# R1075B.net
KiCad netlist of a schematic drawn in EAGLE
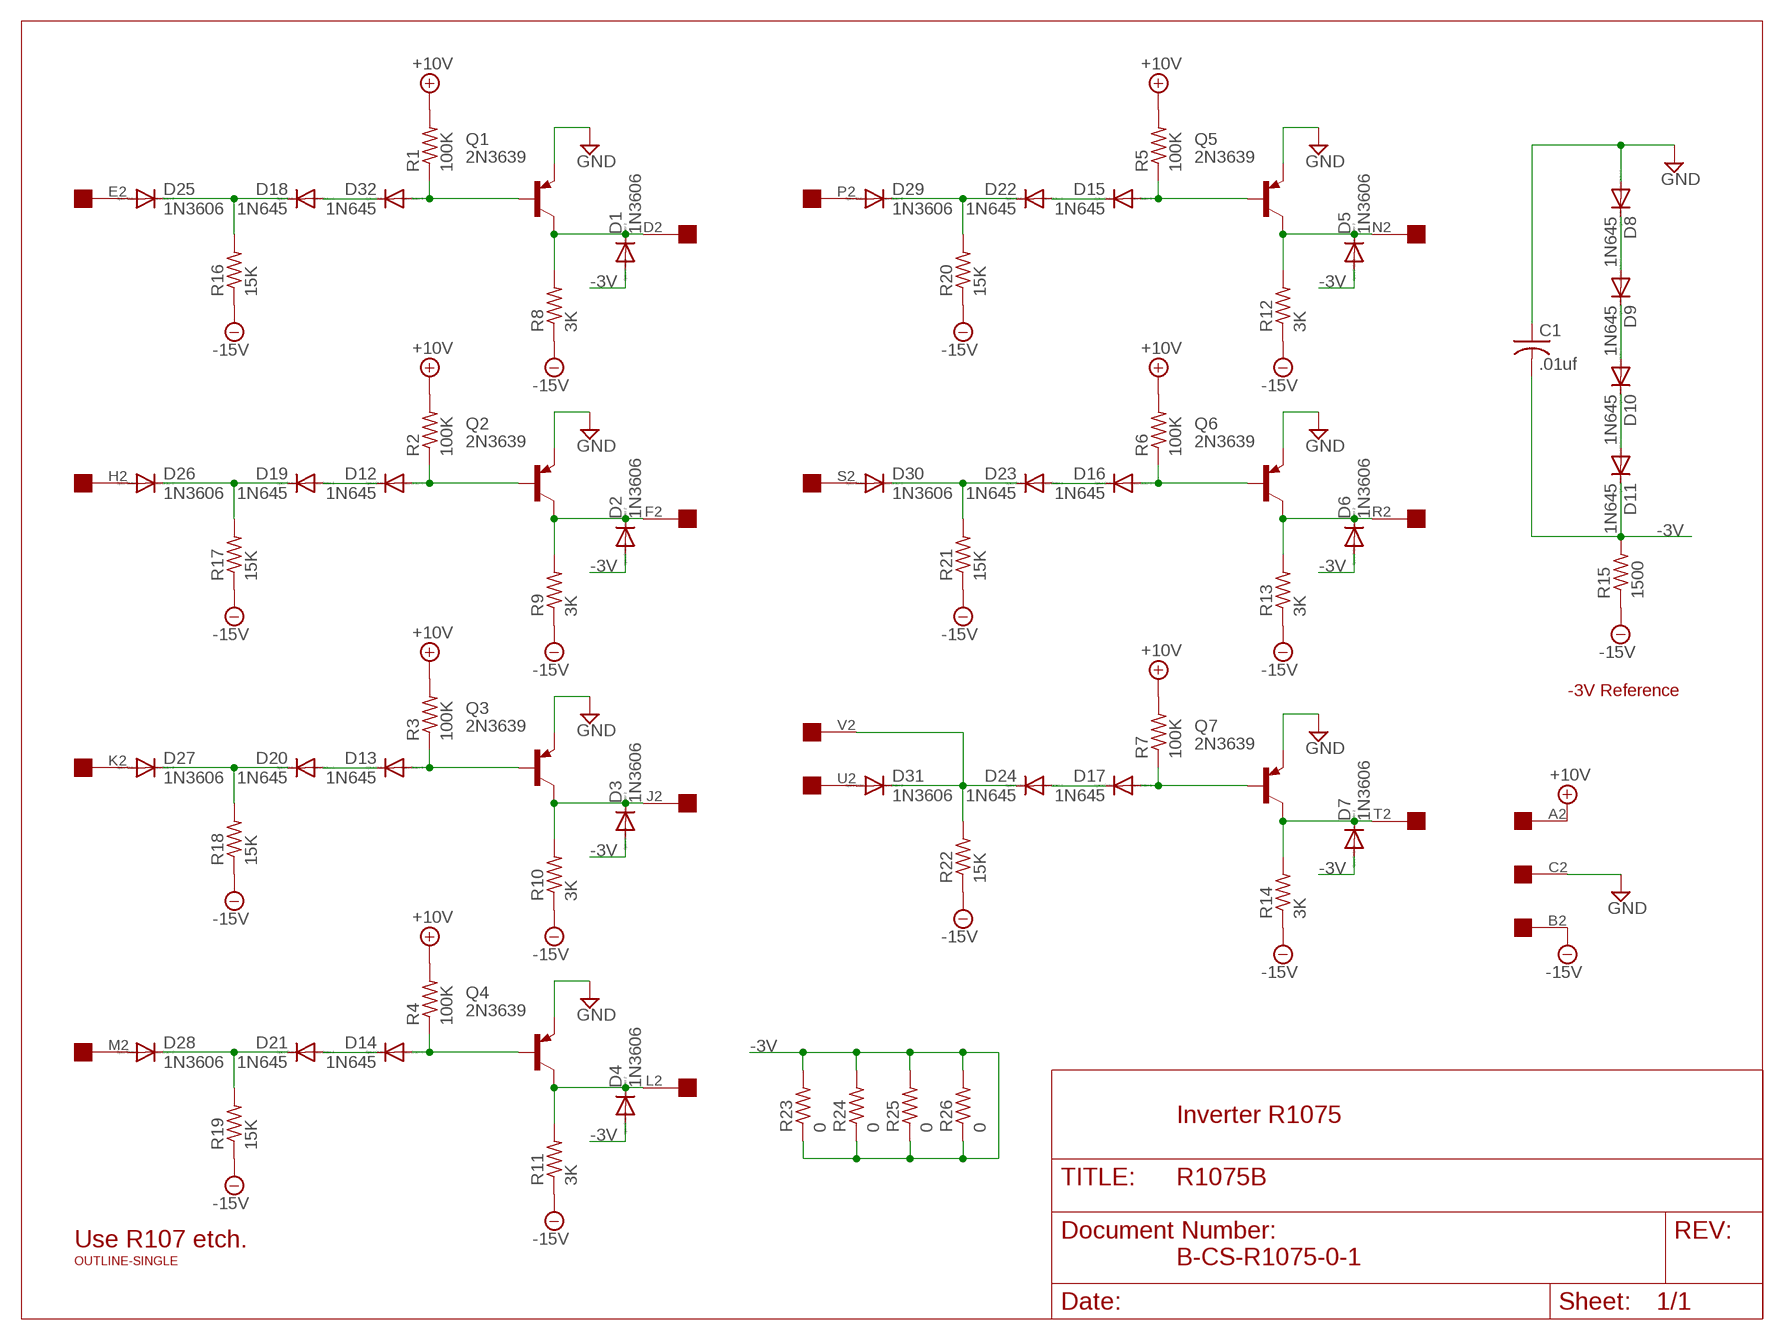
[diagram p0: schematic, sheet 1]

(export (version "E")
  (design (tool "Eeschema 10.0.6"))
  (components
    (comp (ref "C1")
      (value ".01uf")
      (footprint "eagle-import:C063-025X075")
      (libsource (lib "eagle-import") (part "C-US"))
    )
    (comp (ref "D1")
      (value "1N3606")
      (footprint "eagle-import:DO35-10")
      (libsource (lib "eagle-import") (part "1N4148DO35-10"))
    )
    (comp (ref "D2")
      (value "1N3606")
      (footprint "eagle-import:DO35-10")
      (libsource (lib "eagle-import") (part "1N4148DO35-10"))
    )
    (comp (ref "D3")
      (value "1N3606")
      (footprint "eagle-import:DO35-10")
      (libsource (lib "eagle-import") (part "1N4148DO35-10"))
    )
    (comp (ref "D4")
      (value "1N3606")
      (footprint "eagle-import:DO35-10")
      (libsource (lib "eagle-import") (part "1N4148DO35-10"))
    )
    (comp (ref "D5")
      (value "1N3606")
      (footprint "eagle-import:DO35-10")
      (libsource (lib "eagle-import") (part "1N4148DO35-10"))
    )
    (comp (ref "D6")
      (value "1N3606")
      (footprint "eagle-import:DO35-10")
      (libsource (lib "eagle-import") (part "1N4148DO35-10"))
    )
    (comp (ref "D7")
      (value "1N3606")
      (footprint "eagle-import:DO35-10")
      (libsource (lib "eagle-import") (part "1N4148DO35-10"))
    )
    (comp (ref "D8")
      (value "1N645")
      (footprint "eagle-import:DO35-10")
      (libsource (lib "eagle-import") (part "1N4148DO35-10"))
    )
    (comp (ref "D9")
      (value "1N645")
      (footprint "eagle-import:DO35-10")
      (libsource (lib "eagle-import") (part "1N4148DO35-10"))
    )
    (comp (ref "D10")
      (value "1N645")
      (footprint "eagle-import:DO35-10")
      (libsource (lib "eagle-import") (part "1N4148DO35-10"))
    )
    (comp (ref "D11")
      (value "1N645")
      (footprint "eagle-import:DO35-10")
      (libsource (lib "eagle-import") (part "1N4148DO35-10"))
    )
    (comp (ref "D12")
      (value "1N645")
      (footprint "eagle-import:DO35-10")
      (libsource (lib "eagle-import") (part "1N4148DO35-10"))
    )
    (comp (ref "D13")
      (value "1N645")
      (footprint "eagle-import:DO35-10")
      (libsource (lib "eagle-import") (part "1N4148DO35-10"))
    )
    (comp (ref "D14")
      (value "1N645")
      (footprint "eagle-import:DO35-10")
      (libsource (lib "eagle-import") (part "1N4148DO35-10"))
    )
    (comp (ref "D15")
      (value "1N645")
      (footprint "eagle-import:DO35-10")
      (libsource (lib "eagle-import") (part "1N4148DO35-10"))
    )
    (comp (ref "D16")
      (value "1N645")
      (footprint "eagle-import:DO35-10")
      (libsource (lib "eagle-import") (part "1N4148DO35-10"))
    )
    (comp (ref "D17")
      (value "1N645")
      (footprint "eagle-import:DO35-10")
      (libsource (lib "eagle-import") (part "1N4148DO35-10"))
    )
    (comp (ref "D18")
      (value "1N645")
      (footprint "eagle-import:DO35-10")
      (libsource (lib "eagle-import") (part "1N4148DO35-10"))
    )
    (comp (ref "D19")
      (value "1N645")
      (footprint "eagle-import:DO35-10")
      (libsource (lib "eagle-import") (part "1N4148DO35-10"))
    )
    (comp (ref "D20")
      (value "1N645")
      (footprint "eagle-import:DO35-10")
      (libsource (lib "eagle-import") (part "1N4148DO35-10"))
    )
    (comp (ref "D21")
      (value "1N645")
      (footprint "eagle-import:DO35-10")
      (libsource (lib "eagle-import") (part "1N4148DO35-10"))
    )
    (comp (ref "D22")
      (value "1N645")
      (footprint "eagle-import:DO35-10")
      (libsource (lib "eagle-import") (part "1N4148DO35-10"))
    )
    (comp (ref "D23")
      (value "1N645")
      (footprint "eagle-import:DO35-10")
      (libsource (lib "eagle-import") (part "1N4148DO35-10"))
    )
    (comp (ref "D24")
      (value "1N645")
      (footprint "eagle-import:DO35-10")
      (libsource (lib "eagle-import") (part "1N4148DO35-10"))
    )
    (comp (ref "D25")
      (value "1N3606")
      (footprint "eagle-import:DO35-10")
      (libsource (lib "eagle-import") (part "1N4148DO35-10"))
    )
    (comp (ref "D26")
      (value "1N3606")
      (footprint "eagle-import:DO35-10")
      (libsource (lib "eagle-import") (part "1N4148DO35-10"))
    )
    (comp (ref "D27")
      (value "1N3606")
      (footprint "eagle-import:DO35-10")
      (libsource (lib "eagle-import") (part "1N4148DO35-10"))
    )
    (comp (ref "D28")
      (value "1N3606")
      (footprint "eagle-import:DO35-10")
      (libsource (lib "eagle-import") (part "1N4148DO35-10"))
    )
    (comp (ref "D29")
      (value "1N3606")
      (footprint "eagle-import:DO35-10")
      (libsource (lib "eagle-import") (part "1N4148DO35-10"))
    )
    (comp (ref "D30")
      (value "1N3606")
      (footprint "eagle-import:DO35-10")
      (libsource (lib "eagle-import") (part "1N4148DO35-10"))
    )
    (comp (ref "D31")
      (value "1N3606")
      (footprint "eagle-import:DO35-10")
      (libsource (lib "eagle-import") (part "1N4148DO35-10"))
    )
    (comp (ref "D32")
      (value "1N645")
      (footprint "eagle-import:DO35-10")
      (libsource (lib "eagle-import") (part "1N4148DO35-10"))
    )
    (comp (ref "Q1")
      (value "2N3639")
      (footprint "eagle-import:TO39")
      (libsource (lib "eagle-import") (part "2N3637"))
    )
    (comp (ref "Q2")
      (value "2N3639")
      (footprint "eagle-import:TO39")
      (libsource (lib "eagle-import") (part "2N3637"))
    )
    (comp (ref "Q3")
      (value "2N3639")
      (footprint "eagle-import:TO39")
      (libsource (lib "eagle-import") (part "2N3637"))
    )
    (comp (ref "Q4")
      (value "2N3639")
      (footprint "eagle-import:TO39")
      (libsource (lib "eagle-import") (part "2N3637"))
    )
    (comp (ref "Q5")
      (value "2N3639")
      (footprint "eagle-import:TO39")
      (libsource (lib "eagle-import") (part "2N3637"))
    )
    (comp (ref "Q6")
      (value "2N3639")
      (footprint "eagle-import:TO39")
      (libsource (lib "eagle-import") (part "2N3637"))
    )
    (comp (ref "Q7")
      (value "2N3639")
      (footprint "eagle-import:TO39")
      (libsource (lib "eagle-import") (part "2N3637"))
    )
    (comp (ref "R1")
      (value "100K")
      (footprint "eagle-import:0207_10")
      (libsource (lib "eagle-import") (part "R-US_0207/10"))
    )
    (comp (ref "R2")
      (value "100K")
      (footprint "eagle-import:0207_10")
      (libsource (lib "eagle-import") (part "R-US_0207/10"))
    )
    (comp (ref "R3")
      (value "100K")
      (footprint "eagle-import:0207_10")
      (libsource (lib "eagle-import") (part "R-US_0207/10"))
    )
    (comp (ref "R4")
      (value "100K")
      (footprint "eagle-import:0207_10")
      (libsource (lib "eagle-import") (part "R-US_0207/10"))
    )
    (comp (ref "R5")
      (value "100K")
      (footprint "eagle-import:0207_10")
      (libsource (lib "eagle-import") (part "R-US_0207/10"))
    )
    (comp (ref "R6")
      (value "100K")
      (footprint "eagle-import:0207_10")
      (libsource (lib "eagle-import") (part "R-US_0207/10"))
    )
    (comp (ref "R7")
      (value "100K")
      (footprint "eagle-import:0207_10")
      (libsource (lib "eagle-import") (part "R-US_0207/10"))
    )
    (comp (ref "R8")
      (value "3K")
      (footprint "eagle-import:0207_10")
      (libsource (lib "eagle-import") (part "R-US_0207/10"))
    )
    (comp (ref "R9")
      (value "3K")
      (footprint "eagle-import:0207_10")
      (libsource (lib "eagle-import") (part "R-US_0207/10"))
    )
    (comp (ref "R10")
      (value "3K")
      (footprint "eagle-import:0207_10")
      (libsource (lib "eagle-import") (part "R-US_0207/10"))
    )
    (comp (ref "R11")
      (value "3K")
      (footprint "eagle-import:0207_10")
      (libsource (lib "eagle-import") (part "R-US_0207/10"))
    )
    (comp (ref "R12")
      (value "3K")
      (footprint "eagle-import:0207_10")
      (libsource (lib "eagle-import") (part "R-US_0207/10"))
    )
    (comp (ref "R13")
      (value "3K")
      (footprint "eagle-import:0207_10")
      (libsource (lib "eagle-import") (part "R-US_0207/10"))
    )
    (comp (ref "R14")
      (value "3K")
      (footprint "eagle-import:0207_10")
      (libsource (lib "eagle-import") (part "R-US_0207/10"))
    )
    (comp (ref "R15")
      (value "1500")
      (footprint "eagle-import:0207_10")
      (libsource (lib "eagle-import") (part "R-US_0207/10"))
    )
    (comp (ref "R16")
      (value "15K")
      (footprint "eagle-import:0207_10")
      (libsource (lib "eagle-import") (part "R-US_0207/10"))
    )
    (comp (ref "R17")
      (value "15K")
      (footprint "eagle-import:0207_10")
      (libsource (lib "eagle-import") (part "R-US_0207/10"))
    )
    (comp (ref "R18")
      (value "15K")
      (footprint "eagle-import:0207_10")
      (libsource (lib "eagle-import") (part "R-US_0207/10"))
    )
    (comp (ref "R19")
      (value "15K")
      (footprint "eagle-import:0207_10")
      (libsource (lib "eagle-import") (part "R-US_0207/10"))
    )
    (comp (ref "R20")
      (value "15K")
      (footprint "eagle-import:0207_10")
      (libsource (lib "eagle-import") (part "R-US_0207/10"))
    )
    (comp (ref "R21")
      (value "15K")
      (footprint "eagle-import:0207_10")
      (libsource (lib "eagle-import") (part "R-US_0207/10"))
    )
    (comp (ref "R22")
      (value "15K")
      (footprint "eagle-import:0207_10")
      (libsource (lib "eagle-import") (part "R-US_0207/10"))
    )
    (comp (ref "R23")
      (value "0")
      (footprint "eagle-import:0207_10")
      (libsource (lib "eagle-import") (part "R-US_0207/10"))
    )
    (comp (ref "R24")
      (value "0")
      (footprint "eagle-import:0207_10")
      (libsource (lib "eagle-import") (part "R-US_0207/10"))
    )
    (comp (ref "R25")
      (value "0")
      (footprint "eagle-import:0207_10")
      (libsource (lib "eagle-import") (part "R-US_0207/10"))
    )
    (comp (ref "R26")
      (value "0")
      (footprint "eagle-import:0207_10")
      (libsource (lib "eagle-import") (part "R-US_0207/10"))
    )
    (comp (ref "U$1")
      (value "OUTLINE-SINGLE")
      (footprint "eagle-import:SINGLE")
      (libsource (lib "eagle-import") (part "OUTLINE-SINGLE"))
    )
    (comp (ref "U$2")
      (value "EDGE-1")
      (footprint "eagle-import:EDGE-CON1")
      (libsource (lib "eagle-import") (part "EDGE-1"))
    )
  )
  (nets
    (net (code "1") (name "+10V") (class "Default")
      (node (ref "R1") (pin "2") (pinfunction "2_2") (pintype "passive"))
      (node (ref "R2") (pin "2") (pinfunction "2_2") (pintype "passive"))
      (node (ref "R3") (pin "2") (pinfunction "2_2") (pintype "passive"))
      (node (ref "R4") (pin "2") (pinfunction "2_2") (pintype "passive"))
      (node (ref "R5") (pin "2") (pinfunction "2_2") (pintype "passive"))
      (node (ref "R6") (pin "2") (pinfunction "2_2") (pintype "passive"))
      (node (ref "R7") (pin "2") (pinfunction "2_2") (pintype "passive"))
      (node (ref "U$2") (pin "A2") (pinfunction "1_A2") (pintype "bidirectional"))
    )
    (net (code "2") (name "-15V") (class "Default")
      (node (ref "R10") (pin "1") (pinfunction "1_1") (pintype "passive"))
      (node (ref "R11") (pin "1") (pinfunction "1_1") (pintype "passive"))
      (node (ref "R12") (pin "1") (pinfunction "1_1") (pintype "passive"))
      (node (ref "R13") (pin "1") (pinfunction "1_1") (pintype "passive"))
      (node (ref "R14") (pin "1") (pinfunction "1_1") (pintype "passive"))
      (node (ref "R15") (pin "1") (pinfunction "1_1") (pintype "passive"))
      (node (ref "R16") (pin "1") (pinfunction "1_1") (pintype "passive"))
      (node (ref "R17") (pin "1") (pinfunction "1_1") (pintype "passive"))
      (node (ref "R18") (pin "1") (pinfunction "1_1") (pintype "passive"))
      (node (ref "R19") (pin "1") (pinfunction "1_1") (pintype "passive"))
      (node (ref "R20") (pin "1") (pinfunction "1_1") (pintype "passive"))
      (node (ref "R21") (pin "1") (pinfunction "1_1") (pintype "passive"))
      (node (ref "R22") (pin "1") (pinfunction "1_1") (pintype "passive"))
      (node (ref "R8") (pin "1") (pinfunction "1_1") (pintype "passive"))
      (node (ref "R9") (pin "1") (pinfunction "1_1") (pintype "passive"))
      (node (ref "U$2") (pin "B2") (pinfunction "1_B2") (pintype "bidirectional"))
    )
    (net (code "3") (name "/-3V") (class "Default")
      (node (ref "C1") (pin "2") (pinfunction "2_2") (pintype "passive"))
      (node (ref "D1") (pin "A") (pinfunction "A_A") (pintype "passive"))
      (node (ref "D11") (pin "C") (pinfunction "C_C") (pintype "passive"))
      (node (ref "D2") (pin "A") (pinfunction "A_A") (pintype "passive"))
      (node (ref "D3") (pin "A") (pinfunction "A_A") (pintype "passive"))
      (node (ref "D4") (pin "A") (pinfunction "A_A") (pintype "passive"))
      (node (ref "D5") (pin "A") (pinfunction "A_A") (pintype "passive"))
      (node (ref "D6") (pin "A") (pinfunction "A_A") (pintype "passive"))
      (node (ref "D7") (pin "A") (pinfunction "A_A") (pintype "passive"))
      (node (ref "R15") (pin "2") (pinfunction "2_2") (pintype "passive"))
      (node (ref "R23") (pin "1") (pinfunction "1_1") (pintype "passive"))
      (node (ref "R23") (pin "2") (pinfunction "2_2") (pintype "passive"))
      (node (ref "R24") (pin "1") (pinfunction "1_1") (pintype "passive"))
      (node (ref "R24") (pin "2") (pinfunction "2_2") (pintype "passive"))
      (node (ref "R25") (pin "1") (pinfunction "1_1") (pintype "passive"))
      (node (ref "R25") (pin "2") (pinfunction "2_2") (pintype "passive"))
      (node (ref "R26") (pin "1") (pinfunction "1_1") (pintype "passive"))
      (node (ref "R26") (pin "2") (pinfunction "2_2") (pintype "passive"))
    )
    (net (code "4") (name "GND") (class "Default")
      (node (ref "C1") (pin "1") (pinfunction "1_1") (pintype "passive"))
      (node (ref "D8") (pin "A") (pinfunction "A_A") (pintype "passive"))
      (node (ref "Q1") (pin "1") (pinfunction "E_1") (pintype "passive"))
      (node (ref "Q2") (pin "1") (pinfunction "E_1") (pintype "passive"))
      (node (ref "Q3") (pin "1") (pinfunction "E_1") (pintype "passive"))
      (node (ref "Q4") (pin "1") (pinfunction "E_1") (pintype "passive"))
      (node (ref "Q5") (pin "1") (pinfunction "E_1") (pintype "passive"))
      (node (ref "Q6") (pin "1") (pinfunction "E_1") (pintype "passive"))
      (node (ref "Q7") (pin "1") (pinfunction "E_1") (pintype "passive"))
      (node (ref "U$2") (pin "C2") (pinfunction "1_C2") (pintype "bidirectional"))
    )
    (net (code "5") (name "Net-(D8-PadC)") (class "Default")
      (node (ref "D8") (pin "C") (pinfunction "C_C") (pintype "passive"))
      (node (ref "D9") (pin "A") (pinfunction "A_A") (pintype "passive"))
    )
    (net (code "6") (name "Net-(D10-PadA)") (class "Default")
      (node (ref "D10") (pin "A") (pinfunction "A_A") (pintype "passive"))
      (node (ref "D9") (pin "C") (pinfunction "C_C") (pintype "passive"))
    )
    (net (code "7") (name "Net-(D10-PadC)") (class "Default")
      (node (ref "D10") (pin "C") (pinfunction "C_C") (pintype "passive"))
      (node (ref "D11") (pin "A") (pinfunction "A_A") (pintype "passive"))
    )
    (net (code "8") (name "Net-(D12-PadC)") (class "Default")
      (node (ref "D12") (pin "C") (pinfunction "C_C") (pintype "passive"))
      (node (ref "D19") (pin "A") (pinfunction "A_A") (pintype "passive"))
    )
    (net (code "9") (name "Net-(D13-PadC)") (class "Default")
      (node (ref "D13") (pin "C") (pinfunction "C_C") (pintype "passive"))
      (node (ref "D20") (pin "A") (pinfunction "A_A") (pintype "passive"))
    )
    (net (code "10") (name "Net-(D14-PadC)") (class "Default")
      (node (ref "D14") (pin "C") (pinfunction "C_C") (pintype "passive"))
      (node (ref "D21") (pin "A") (pinfunction "A_A") (pintype "passive"))
    )
    (net (code "11") (name "Net-(D15-PadC)") (class "Default")
      (node (ref "D15") (pin "C") (pinfunction "C_C") (pintype "passive"))
      (node (ref "D22") (pin "A") (pinfunction "A_A") (pintype "passive"))
    )
    (net (code "12") (name "Net-(D16-PadC)") (class "Default")
      (node (ref "D16") (pin "C") (pinfunction "C_C") (pintype "passive"))
      (node (ref "D23") (pin "A") (pinfunction "A_A") (pintype "passive"))
    )
    (net (code "13") (name "Net-(D17-PadC)") (class "Default")
      (node (ref "D17") (pin "C") (pinfunction "C_C") (pintype "passive"))
      (node (ref "D24") (pin "A") (pinfunction "A_A") (pintype "passive"))
    )
    (net (code "14") (name "Net-(D18-PadA)") (class "Default")
      (node (ref "D18") (pin "A") (pinfunction "A_A") (pintype "passive"))
      (node (ref "D32") (pin "C") (pinfunction "C_C") (pintype "passive"))
    )
    (net (code "15") (name "Net-(D18-PadC)") (class "Default")
      (node (ref "D18") (pin "C") (pinfunction "C_C") (pintype "passive"))
      (node (ref "D25") (pin "C") (pinfunction "C_C") (pintype "passive"))
      (node (ref "R16") (pin "2") (pinfunction "2_2") (pintype "passive"))
    )
    (net (code "16") (name "Net-(D19-PadC)") (class "Default")
      (node (ref "D19") (pin "C") (pinfunction "C_C") (pintype "passive"))
      (node (ref "D26") (pin "C") (pinfunction "C_C") (pintype "passive"))
      (node (ref "R17") (pin "2") (pinfunction "2_2") (pintype "passive"))
    )
    (net (code "17") (name "Net-(D20-PadC)") (class "Default")
      (node (ref "D20") (pin "C") (pinfunction "C_C") (pintype "passive"))
      (node (ref "D27") (pin "C") (pinfunction "C_C") (pintype "passive"))
      (node (ref "R18") (pin "2") (pinfunction "2_2") (pintype "passive"))
    )
    (net (code "18") (name "Net-(D21-PadC)") (class "Default")
      (node (ref "D21") (pin "C") (pinfunction "C_C") (pintype "passive"))
      (node (ref "D28") (pin "C") (pinfunction "C_C") (pintype "passive"))
      (node (ref "R19") (pin "2") (pinfunction "2_2") (pintype "passive"))
    )
    (net (code "19") (name "Net-(D22-PadC)") (class "Default")
      (node (ref "D22") (pin "C") (pinfunction "C_C") (pintype "passive"))
      (node (ref "D29") (pin "C") (pinfunction "C_C") (pintype "passive"))
      (node (ref "R20") (pin "2") (pinfunction "2_2") (pintype "passive"))
    )
    (net (code "20") (name "Net-(D23-PadC)") (class "Default")
      (node (ref "D23") (pin "C") (pinfunction "C_C") (pintype "passive"))
      (node (ref "D30") (pin "C") (pinfunction "C_C") (pintype "passive"))
      (node (ref "R21") (pin "2") (pinfunction "2_2") (pintype "passive"))
    )
    (net (code "21") (name "Net-(Q1-B)") (class "Default")
      (node (ref "D32") (pin "A") (pinfunction "A_A") (pintype "passive"))
      (node (ref "Q1") (pin "2") (pinfunction "B_2") (pintype "passive"))
      (node (ref "R1") (pin "1") (pinfunction "1_1") (pintype "passive"))
    )
    (net (code "22") (name "Net-(Q1-C)") (class "Default")
      (node (ref "D1") (pin "C") (pinfunction "C_C") (pintype "passive"))
      (node (ref "Q1") (pin "3") (pinfunction "C_3") (pintype "passive"))
      (node (ref "R8") (pin "2") (pinfunction "2_2") (pintype "passive"))
      (node (ref "U$2") (pin "D2") (pinfunction "1_D2") (pintype "bidirectional"))
    )
    (net (code "23") (name "Net-(Q2-B)") (class "Default")
      (node (ref "D12") (pin "A") (pinfunction "A_A") (pintype "passive"))
      (node (ref "Q2") (pin "2") (pinfunction "B_2") (pintype "passive"))
      (node (ref "R2") (pin "1") (pinfunction "1_1") (pintype "passive"))
    )
    (net (code "24") (name "Net-(Q2-C)") (class "Default")
      (node (ref "D2") (pin "C") (pinfunction "C_C") (pintype "passive"))
      (node (ref "Q2") (pin "3") (pinfunction "C_3") (pintype "passive"))
      (node (ref "R9") (pin "2") (pinfunction "2_2") (pintype "passive"))
      (node (ref "U$2") (pin "F2") (pinfunction "1_F2") (pintype "bidirectional"))
    )
    (net (code "25") (name "Net-(Q3-B)") (class "Default")
      (node (ref "D13") (pin "A") (pinfunction "A_A") (pintype "passive"))
      (node (ref "Q3") (pin "2") (pinfunction "B_2") (pintype "passive"))
      (node (ref "R3") (pin "1") (pinfunction "1_1") (pintype "passive"))
    )
    (net (code "26") (name "Net-(Q3-C)") (class "Default")
      (node (ref "D3") (pin "C") (pinfunction "C_C") (pintype "passive"))
      (node (ref "Q3") (pin "3") (pinfunction "C_3") (pintype "passive"))
      (node (ref "R10") (pin "2") (pinfunction "2_2") (pintype "passive"))
      (node (ref "U$2") (pin "J2") (pinfunction "1_J2") (pintype "bidirectional"))
    )
    (net (code "27") (name "Net-(Q4-B)") (class "Default")
      (node (ref "D14") (pin "A") (pinfunction "A_A") (pintype "passive"))
      (node (ref "Q4") (pin "2") (pinfunction "B_2") (pintype "passive"))
      (node (ref "R4") (pin "1") (pinfunction "1_1") (pintype "passive"))
    )
    (net (code "28") (name "Net-(Q4-C)") (class "Default")
      (node (ref "D4") (pin "C") (pinfunction "C_C") (pintype "passive"))
      (node (ref "Q4") (pin "3") (pinfunction "C_3") (pintype "passive"))
      (node (ref "R11") (pin "2") (pinfunction "2_2") (pintype "passive"))
      (node (ref "U$2") (pin "L2") (pinfunction "1_L2") (pintype "bidirectional"))
    )
    (net (code "29") (name "Net-(Q5-B)") (class "Default")
      (node (ref "D15") (pin "A") (pinfunction "A_A") (pintype "passive"))
      (node (ref "Q5") (pin "2") (pinfunction "B_2") (pintype "passive"))
      (node (ref "R5") (pin "1") (pinfunction "1_1") (pintype "passive"))
    )
    (net (code "30") (name "Net-(Q5-C)") (class "Default")
      (node (ref "D5") (pin "C") (pinfunction "C_C") (pintype "passive"))
      (node (ref "Q5") (pin "3") (pinfunction "C_3") (pintype "passive"))
      (node (ref "R12") (pin "2") (pinfunction "2_2") (pintype "passive"))
      (node (ref "U$2") (pin "N2") (pinfunction "1_N2") (pintype "bidirectional"))
    )
    (net (code "31") (name "Net-(Q6-B)") (class "Default")
      (node (ref "D16") (pin "A") (pinfunction "A_A") (pintype "passive"))
      (node (ref "Q6") (pin "2") (pinfunction "B_2") (pintype "passive"))
      (node (ref "R6") (pin "1") (pinfunction "1_1") (pintype "passive"))
    )
    (net (code "32") (name "Net-(Q6-C)") (class "Default")
      (node (ref "D6") (pin "C") (pinfunction "C_C") (pintype "passive"))
      (node (ref "Q6") (pin "3") (pinfunction "C_3") (pintype "passive"))
      (node (ref "R13") (pin "2") (pinfunction "2_2") (pintype "passive"))
      (node (ref "U$2") (pin "R2") (pinfunction "1_R2") (pintype "bidirectional"))
    )
    (net (code "33") (name "Net-(Q7-B)") (class "Default")
      (node (ref "D17") (pin "A") (pinfunction "A_A") (pintype "passive"))
      (node (ref "Q7") (pin "2") (pinfunction "B_2") (pintype "passive"))
      (node (ref "R7") (pin "1") (pinfunction "1_1") (pintype "passive"))
    )
    (net (code "34") (name "Net-(Q7-C)") (class "Default")
      (node (ref "D7") (pin "C") (pinfunction "C_C") (pintype "passive"))
      (node (ref "Q7") (pin "3") (pinfunction "C_3") (pintype "passive"))
      (node (ref "R14") (pin "2") (pinfunction "2_2") (pintype "passive"))
      (node (ref "U$2") (pin "T2") (pinfunction "1_T2") (pintype "bidirectional"))
    )
    (net (code "35") (name "Net-(U$2E-1)") (class "Default")
      (node (ref "D25") (pin "A") (pinfunction "A_A") (pintype "passive"))
      (node (ref "U$2") (pin "E2") (pinfunction "1_E2") (pintype "bidirectional"))
    )
    (net (code "36") (name "Net-(U$2G-1)") (class "Default")
      (node (ref "D26") (pin "A") (pinfunction "A_A") (pintype "passive"))
      (node (ref "U$2") (pin "H2") (pinfunction "1_H2") (pintype "bidirectional"))
    )
    (net (code "37") (name "Net-(U$2I-1)") (class "Default")
      (node (ref "D27") (pin "A") (pinfunction "A_A") (pintype "passive"))
      (node (ref "U$2") (pin "K2") (pinfunction "1_K2") (pintype "bidirectional"))
    )
    (net (code "38") (name "Net-(U$2K-1)") (class "Default")
      (node (ref "D28") (pin "A") (pinfunction "A_A") (pintype "passive"))
      (node (ref "U$2") (pin "M2") (pinfunction "1_M2") (pintype "bidirectional"))
    )
    (net (code "39") (name "Net-(U$2M-1)") (class "Default")
      (node (ref "D29") (pin "A") (pinfunction "A_A") (pintype "passive"))
      (node (ref "U$2") (pin "P2") (pinfunction "1_P2") (pintype "bidirectional"))
    )
    (net (code "40") (name "Net-(U$2O-1)") (class "Default")
      (node (ref "D30") (pin "A") (pinfunction "A_A") (pintype "passive"))
      (node (ref "U$2") (pin "S2") (pinfunction "1_S2") (pintype "bidirectional"))
    )
    (net (code "41") (name "Net-(U$2Q-1)") (class "Default")
      (node (ref "D31") (pin "A") (pinfunction "A_A") (pintype "passive"))
      (node (ref "U$2") (pin "U2") (pinfunction "1_U2") (pintype "bidirectional"))
    )
    (net (code "42") (name "Net-(U$2R-1)") (class "Default")
      (node (ref "D24") (pin "C") (pinfunction "C_C") (pintype "passive"))
      (node (ref "D31") (pin "C") (pinfunction "C_C") (pintype "passive"))
      (node (ref "R22") (pin "2") (pinfunction "2_2") (pintype "passive"))
      (node (ref "U$2") (pin "V2") (pinfunction "1_V2") (pintype "bidirectional"))
    )
  )
)
